# Power_Reg.net
KiCad netlist of a schematic drawn in EAGLE
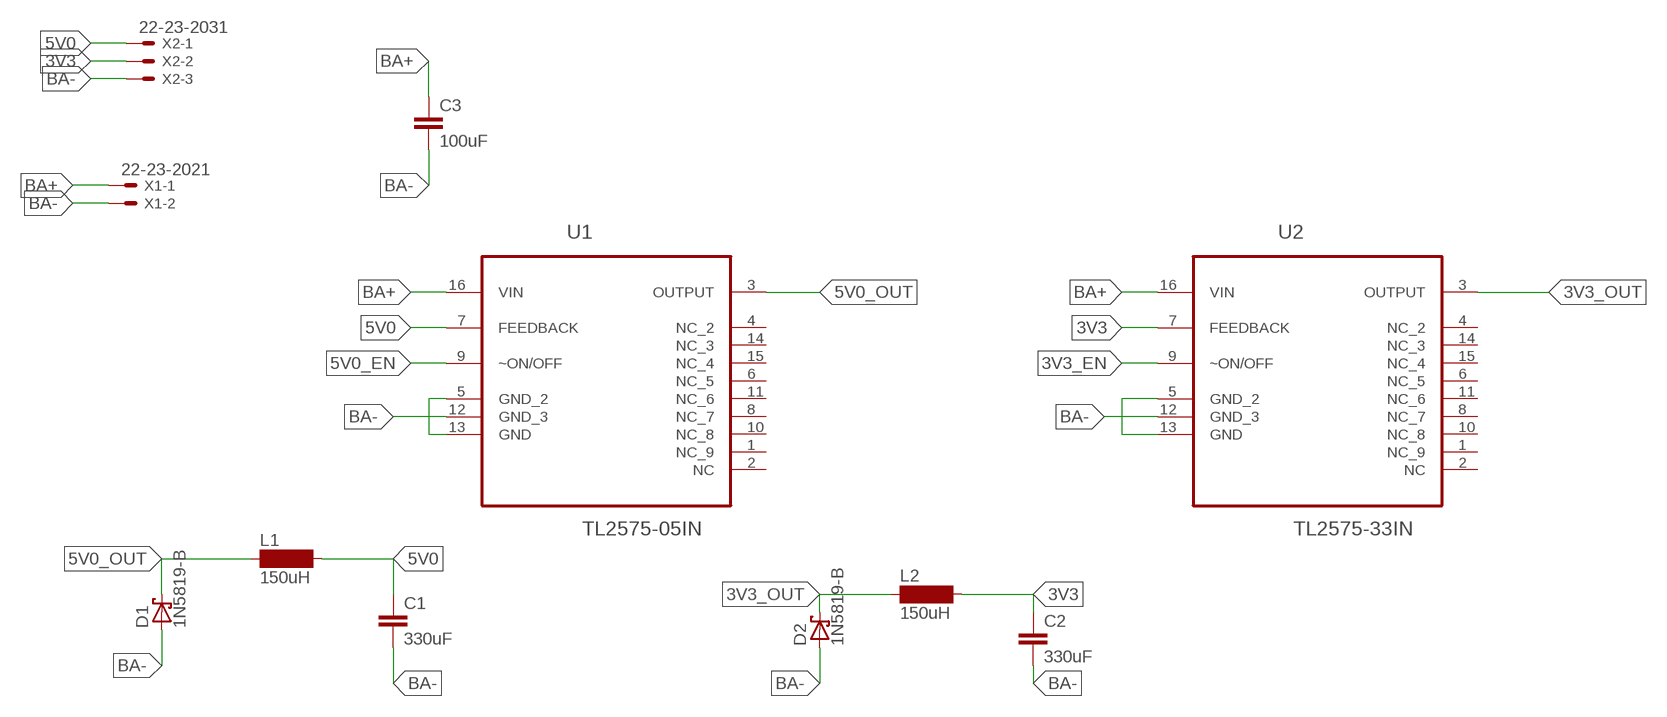
[diagram p0: schematic, sheet 1]

(export (version "E")
  (design (tool "Eeschema 10.0.6"))
  (components
    (comp (ref "C1")
      (value "330uF")
      (footprint "eagle-import:C5B3.5")
      (libsource (lib "eagle-import") (part "C5/3.5"))
    )
    (comp (ref "C2")
      (value "330uF")
      (footprint "eagle-import:C5B3.5")
      (libsource (lib "eagle-import") (part "C5/3.5"))
    )
    (comp (ref "C3")
      (value "100uF")
      (footprint "eagle-import:C5B3.5")
      (libsource (lib "eagle-import") (part "C5/3.5"))
    )
    (comp (ref "D1")
      (value "1N5819-B")
      (footprint "eagle-import:DO41-7.6")
      (libsource (lib "eagle-import") (part "1N5819-B"))
    )
    (comp (ref "D2")
      (value "1N5819-B")
      (footprint "eagle-import:DO41-7.6")
      (libsource (lib "eagle-import") (part "1N5819-B"))
    )
    (comp (ref "L1")
      (value "150uH")
      (footprint "eagle-import:SD8")
      (libsource (lib "eagle-import") (part "SD8"))
    )
    (comp (ref "L2")
      (value "150uH")
      (footprint "eagle-import:SD8")
      (libsource (lib "eagle-import") (part "SD8"))
    )
    (comp (ref "U1")
      (value "TL2575-05IN")
      (footprint "eagle-import:DIP254P762X508-16")
      (fields (field (name "MPN") "TL2575HV-05IN"))
      (libsource (lib "eagle-import") (part "TL2575-05IN"))
    )
    (comp (ref "U2")
      (value "TL2575-33IN")
      (footprint "eagle-import:DIP254P762X508-16")
      (fields (field (name "MPN") "TL2575HV-05IN"))
      (libsource (lib "eagle-import") (part "TL2575-33IN"))
    )
    (comp (ref "X1")
      (value "22-23-2021")
      (footprint "eagle-import:22-23-2021")
      (fields (field (name "MF") "MOLEX"))
      (libsource (lib "eagle-import") (part "22-23-2021"))
    )
    (comp (ref "X2")
      (value "22-23-2031")
      (footprint "eagle-import:22-23-2031")
      (fields (field (name "MF") "MOLEX"))
      (libsource (lib "eagle-import") (part "22-23-2031"))
    )
  )
  (nets
    (net (code "1") (name "3V3") (class "Default")
      (node (ref "C2") (pin "1") (pinfunction "1_1") (pintype "passive"))
      (node (ref "L2") (pin "2") (pinfunction "2_2") (pintype "passive"))
      (node (ref "U2") (pin "7") (pinfunction "FEEDBACK_7") (pintype "bidirectional"))
      (node (ref "X2") (pin "2") (pinfunction "S_2") (pintype "passive"))
    )
    (net (code "2") (name "3V3_EN") (class "Default")
      (node (ref "U2") (pin "9") (pinfunction "~{ON/OFF}_9") (pintype "input"))
    )
    (net (code "3") (name "3V3_OUT") (class "Default")
      (node (ref "D2") (pin "C") (pinfunction "C_C") (pintype "passive"))
      (node (ref "L2") (pin "1") (pinfunction "1_1") (pintype "passive"))
      (node (ref "U2") (pin "3") (pinfunction "OUTPUT_3") (pintype "output"))
    )
    (net (code "4") (name "5V0") (class "Default")
      (node (ref "C1") (pin "1") (pinfunction "1_1") (pintype "passive"))
      (node (ref "L1") (pin "2") (pinfunction "2_2") (pintype "passive"))
      (node (ref "U1") (pin "7") (pinfunction "FEEDBACK_7") (pintype "bidirectional"))
      (node (ref "X2") (pin "1") (pinfunction "S_1") (pintype "passive"))
    )
    (net (code "5") (name "5V0_EN") (class "Default")
      (node (ref "U1") (pin "9") (pinfunction "~{ON/OFF}_9") (pintype "input"))
    )
    (net (code "6") (name "5V0_OUT") (class "Default")
      (node (ref "D1") (pin "C") (pinfunction "C_C") (pintype "passive"))
      (node (ref "L1") (pin "1") (pinfunction "1_1") (pintype "passive"))
      (node (ref "U1") (pin "3") (pinfunction "OUTPUT_3") (pintype "output"))
    )
    (net (code "7") (name "BA+") (class "Default")
      (node (ref "C3") (pin "1") (pinfunction "1_1") (pintype "passive"))
      (node (ref "U1") (pin "16") (pinfunction "VIN_16") (pintype "power_in"))
      (node (ref "U2") (pin "16") (pinfunction "VIN_16") (pintype "power_in"))
      (node (ref "X1") (pin "1") (pinfunction "S_1") (pintype "passive"))
    )
    (net (code "8") (name "BA-") (class "Default")
      (node (ref "C1") (pin "2") (pinfunction "2_2") (pintype "passive"))
      (node (ref "C2") (pin "2") (pinfunction "2_2") (pintype "passive"))
      (node (ref "C3") (pin "2") (pinfunction "2_2") (pintype "passive"))
      (node (ref "D1") (pin "A") (pinfunction "A_A") (pintype "passive"))
      (node (ref "D2") (pin "A") (pinfunction "A_A") (pintype "passive"))
      (node (ref "U1") (pin "12") (pinfunction "GND_3_12") (pintype "passive"))
      (node (ref "U1") (pin "13") (pinfunction "GND_13") (pintype "passive"))
      (node (ref "U1") (pin "5") (pinfunction "GND_2_5") (pintype "passive"))
      (node (ref "U2") (pin "12") (pinfunction "GND_3_12") (pintype "passive"))
      (node (ref "U2") (pin "13") (pinfunction "GND_13") (pintype "passive"))
      (node (ref "U2") (pin "5") (pinfunction "GND_2_5") (pintype "passive"))
      (node (ref "X1") (pin "2") (pinfunction "S_2") (pintype "passive"))
      (node (ref "X2") (pin "3") (pinfunction "S_3") (pintype "passive"))
    )
    (net (code "9") (name "unconnected-(U1-NC-Pad2)") (class "Default")
      (node (ref "U1") (pin "2") (pinfunction "NC_2") (pintype "no_connect"))
    )
    (net (code "10") (name "unconnected-(U1-NC_2-Pad4)") (class "Default")
      (node (ref "U1") (pin "4") (pinfunction "NC_2_4") (pintype "no_connect"))
    )
    (net (code "11") (name "unconnected-(U1-NC_3-Pad14)") (class "Default")
      (node (ref "U1") (pin "14") (pinfunction "NC_3_14") (pintype "no_connect"))
    )
    (net (code "12") (name "unconnected-(U1-NC_4-Pad15)") (class "Default")
      (node (ref "U1") (pin "15") (pinfunction "NC_4_15") (pintype "no_connect"))
    )
    (net (code "13") (name "unconnected-(U1-NC_5-Pad6)") (class "Default")
      (node (ref "U1") (pin "6") (pinfunction "NC_5_6") (pintype "no_connect"))
    )
    (net (code "14") (name "unconnected-(U1-NC_6-Pad11)") (class "Default")
      (node (ref "U1") (pin "11") (pinfunction "NC_6_11") (pintype "no_connect"))
    )
    (net (code "15") (name "unconnected-(U1-NC_7-Pad8)") (class "Default")
      (node (ref "U1") (pin "8") (pinfunction "NC_7_8") (pintype "no_connect"))
    )
    (net (code "16") (name "unconnected-(U1-NC_8-Pad10)") (class "Default")
      (node (ref "U1") (pin "10") (pinfunction "NC_8_10") (pintype "no_connect"))
    )
    (net (code "17") (name "unconnected-(U1-NC_9-Pad1)") (class "Default")
      (node (ref "U1") (pin "1") (pinfunction "NC_9_1") (pintype "no_connect"))
    )
    (net (code "18") (name "unconnected-(U2-NC-Pad2)") (class "Default")
      (node (ref "U2") (pin "2") (pinfunction "NC_2") (pintype "no_connect"))
    )
    (net (code "19") (name "unconnected-(U2-NC_2-Pad4)") (class "Default")
      (node (ref "U2") (pin "4") (pinfunction "NC_2_4") (pintype "no_connect"))
    )
    (net (code "20") (name "unconnected-(U2-NC_3-Pad14)") (class "Default")
      (node (ref "U2") (pin "14") (pinfunction "NC_3_14") (pintype "no_connect"))
    )
    (net (code "21") (name "unconnected-(U2-NC_4-Pad15)") (class "Default")
      (node (ref "U2") (pin "15") (pinfunction "NC_4_15") (pintype "no_connect"))
    )
    (net (code "22") (name "unconnected-(U2-NC_5-Pad6)") (class "Default")
      (node (ref "U2") (pin "6") (pinfunction "NC_5_6") (pintype "no_connect"))
    )
    (net (code "23") (name "unconnected-(U2-NC_6-Pad11)") (class "Default")
      (node (ref "U2") (pin "11") (pinfunction "NC_6_11") (pintype "no_connect"))
    )
    (net (code "24") (name "unconnected-(U2-NC_7-Pad8)") (class "Default")
      (node (ref "U2") (pin "8") (pinfunction "NC_7_8") (pintype "no_connect"))
    )
    (net (code "25") (name "unconnected-(U2-NC_8-Pad10)") (class "Default")
      (node (ref "U2") (pin "10") (pinfunction "NC_8_10") (pintype "no_connect"))
    )
    (net (code "26") (name "unconnected-(U2-NC_9-Pad1)") (class "Default")
      (node (ref "U2") (pin "1") (pinfunction "NC_9_1") (pintype "no_connect"))
    )
  )
)
